# esp32_ornith_1_0_2.net
KiCad netlist of a schematic drawn in EAGLE
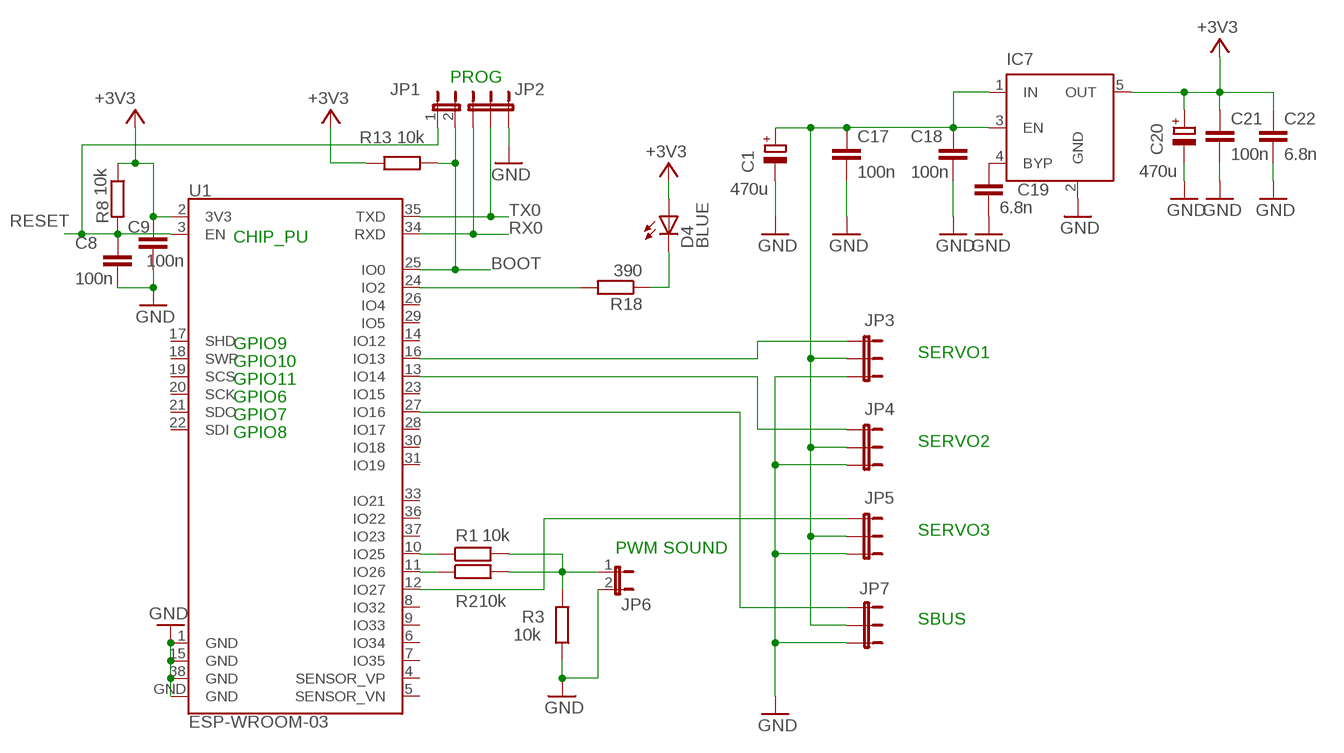
[diagram p0: schematic, sheet 1]

(export (version "E")
  (design (tool "Eeschema 10.0.6"))
  (components
    (comp (ref "C1")
      (value "470u")
      (footprint "eagle-import:SMC_D")
      (libsource (lib "eagle-import") (part "CPOL-EUSMCD"))
    )
    (comp (ref "C8")
      (value "100n")
      (footprint "eagle-import:C0603")
      (libsource (lib "eagle-import") (part "C-EUC0603"))
    )
    (comp (ref "C9")
      (value "100n")
      (footprint "eagle-import:C0603")
      (libsource (lib "eagle-import") (part "C-EUC0603"))
    )
    (comp (ref "C17")
      (value "100n")
      (footprint "eagle-import:C0603K")
      (libsource (lib "eagle-import") (part "C-EUC0603K"))
    )
    (comp (ref "C18")
      (value "100n")
      (footprint "eagle-import:C0603K")
      (libsource (lib "eagle-import") (part "C-EUC0603K"))
    )
    (comp (ref "C19")
      (value "6.8n")
      (footprint "eagle-import:C0603K")
      (libsource (lib "eagle-import") (part "C-EUC0603K"))
    )
    (comp (ref "C20")
      (value "470u")
      (footprint "eagle-import:SMC_D")
      (libsource (lib "eagle-import") (part "CPOL-EUSMCD"))
    )
    (comp (ref "C21")
      (value "100n")
      (footprint "eagle-import:C0603K")
      (libsource (lib "eagle-import") (part "C-EUC0603K"))
    )
    (comp (ref "C22")
      (value "6.8n")
      (footprint "eagle-import:C0603K")
      (libsource (lib "eagle-import") (part "C-EUC0603K"))
    )
    (comp (ref "D4")
      (value "BLUE")
      (footprint "eagle-import:LED-0603")
      (libsource (lib "eagle-import") (part "LED-BLUE0603"))
    )
    (comp (ref "IC7")
      (value "MIC5219XX")
      (footprint "eagle-import:SOT23-5")
      (libsource (lib "eagle-import") (part "MIC5219XX"))
    )
    (comp (ref "JP1")
      (value "JUMPER-2PTH")
      (footprint "eagle-import:1X02")
      (libsource (lib "eagle-import") (part "JUMPER-2PTH"))
    )
    (comp (ref "JP2")
      (value "JUMPER-3PTH")
      (footprint "eagle-import:1X03")
      (libsource (lib "eagle-import") (part "JUMPER-3PTH"))
    )
    (comp (ref "JP3")
      (value "JUMPER-3PTH")
      (footprint "eagle-import:1X03")
      (libsource (lib "eagle-import") (part "JUMPER-3PTH"))
    )
    (comp (ref "JP4")
      (value "JUMPER-3PTH")
      (footprint "eagle-import:1X03")
      (libsource (lib "eagle-import") (part "JUMPER-3PTH"))
    )
    (comp (ref "JP5")
      (value "JUMPER-3PTH")
      (footprint "eagle-import:1X03")
      (libsource (lib "eagle-import") (part "JUMPER-3PTH"))
    )
    (comp (ref "JP6")
      (value "JUMPER-2PTH")
      (footprint "eagle-import:1X02")
      (libsource (lib "eagle-import") (part "JUMPER-2PTH"))
    )
    (comp (ref "JP7")
      (value "JUMPER-3PTH")
      (footprint "eagle-import:1X03")
      (libsource (lib "eagle-import") (part "JUMPER-3PTH"))
    )
    (comp (ref "R1")
      (value "10k")
      (footprint "eagle-import:R0603")
      (libsource (lib "eagle-import") (part "R-EU_R0603"))
    )
    (comp (ref "R2")
      (value "10k")
      (footprint "eagle-import:R0603")
      (libsource (lib "eagle-import") (part "R-EU_R0603"))
    )
    (comp (ref "R3")
      (value "10k")
      (footprint "eagle-import:R0603")
      (libsource (lib "eagle-import") (part "R-EU_R0603"))
    )
    (comp (ref "R8")
      (value "10k")
      (footprint "eagle-import:R0603")
      (libsource (lib "eagle-import") (part "R-EU_R0603"))
    )
    (comp (ref "R13")
      (value "10k")
      (footprint "eagle-import:R0603")
      (libsource (lib "eagle-import") (part "R-EU_R0603"))
    )
    (comp (ref "R18")
      (value "390")
      (footprint "eagle-import:R0603")
      (libsource (lib "eagle-import") (part "R-EU_R0603"))
    )
    (comp (ref "U1")
      (value "ESP-WROOM-03")
      (footprint "eagle-import:ESP-WROOM-03")
      (libsource (lib "eagle-import") (part "ESP-WROOM-03"))
    )
  )
  (nets
    (net (code "1") (name "+3V3") (class "Default")
      (node (ref "C20") (pin "+") (pinfunction "+_+") (pintype "passive"))
      (node (ref "C21") (pin "1") (pinfunction "1_1") (pintype "passive"))
      (node (ref "C22") (pin "1") (pinfunction "1_1") (pintype "passive"))
      (node (ref "C9") (pin "1") (pinfunction "1_1") (pintype "passive"))
      (node (ref "D4") (pin "A") (pinfunction "A_A") (pintype "passive"))
      (node (ref "IC7") (pin "5") (pinfunction "OUT_5") (pintype "output"))
      (node (ref "R13") (pin "2") (pinfunction "2_2") (pintype "passive"))
      (node (ref "R8") (pin "1") (pinfunction "1_1") (pintype "passive"))
      (node (ref "U1") (pin "2") (pinfunction "3V3_2") (pintype "bidirectional"))
    )
    (net (code "2") (name "/BOOT") (class "Default")
      (node (ref "JP1") (pin "2") (pinfunction "2_2") (pintype "passive"))
      (node (ref "R13") (pin "1") (pinfunction "1_1") (pintype "passive"))
      (node (ref "U1") (pin "25") (pinfunction "IO0_25") (pintype "bidirectional"))
    )
    (net (code "3") (name "/RESET") (class "Default")
      (node (ref "C8") (pin "1") (pinfunction "1_1") (pintype "passive"))
      (node (ref "JP1") (pin "1") (pinfunction "1_1") (pintype "passive"))
      (node (ref "R8") (pin "2") (pinfunction "2_2") (pintype "passive"))
      (node (ref "U1") (pin "3") (pinfunction "EN_3") (pintype "bidirectional"))
    )
    (net (code "4") (name "/RX0") (class "Default")
      (node (ref "JP2") (pin "1") (pinfunction "1_1") (pintype "passive"))
      (node (ref "U1") (pin "34") (pinfunction "RXD_34") (pintype "bidirectional"))
    )
    (net (code "5") (name "/TX0") (class "Default")
      (node (ref "JP2") (pin "2") (pinfunction "2_2") (pintype "passive"))
      (node (ref "U1") (pin "35") (pinfunction "TXD_35") (pintype "bidirectional"))
    )
    (net (code "6") (name "GND") (class "Default")
      (node (ref "C1") (pin "-") (pinfunction "-_-") (pintype "passive"))
      (node (ref "C17") (pin "2") (pinfunction "2_2") (pintype "passive"))
      (node (ref "C18") (pin "2") (pinfunction "2_2") (pintype "passive"))
      (node (ref "C19") (pin "2") (pinfunction "2_2") (pintype "passive"))
      (node (ref "C20") (pin "-") (pinfunction "-_-") (pintype "passive"))
      (node (ref "C21") (pin "2") (pinfunction "2_2") (pintype "passive"))
      (node (ref "C22") (pin "2") (pinfunction "2_2") (pintype "passive"))
      (node (ref "C8") (pin "2") (pinfunction "2_2") (pintype "passive"))
      (node (ref "C9") (pin "2") (pinfunction "2_2") (pintype "passive"))
      (node (ref "IC7") (pin "2") (pinfunction "GND_2") (pintype "power_in"))
      (node (ref "JP2") (pin "3") (pinfunction "3_3") (pintype "passive"))
      (node (ref "JP3") (pin "1") (pinfunction "1_1") (pintype "passive"))
      (node (ref "JP4") (pin "1") (pinfunction "1_1") (pintype "passive"))
      (node (ref "JP5") (pin "1") (pinfunction "1_1") (pintype "passive"))
      (node (ref "JP6") (pin "2") (pinfunction "2_2") (pintype "passive"))
      (node (ref "JP7") (pin "3") (pinfunction "3_3") (pintype "passive"))
      (node (ref "R3") (pin "1") (pinfunction "1_1") (pintype "passive"))
      (node (ref "U1") (pin "1") (pinfunction "GND_1") (pintype "bidirectional"))
      (node (ref "U1") (pin "15") (pinfunction "GND_15") (pintype "bidirectional"))
      (node (ref "U1") (pin "38") (pinfunction "GND_38") (pintype "bidirectional"))
      (node (ref "U1") (pin "GND") (pinfunction "GND_GND") (pintype "bidirectional"))
    )
    (net (code "7") (name "Net-(D4-PadC)") (class "Default")
      (node (ref "D4") (pin "C") (pinfunction "C_C") (pintype "passive"))
      (node (ref "R18") (pin "1") (pinfunction "1_1") (pintype "passive"))
    )
    (net (code "8") (name "Net-(IC7-BYP)") (class "Default")
      (node (ref "C19") (pin "1") (pinfunction "1_1") (pintype "passive"))
      (node (ref "IC7") (pin "4") (pinfunction "BYP_4") (pintype "passive"))
    )
    (net (code "9") (name "Net-(IC7-EN)") (class "Default")
      (node (ref "C1") (pin "+") (pinfunction "+_+") (pintype "passive"))
      (node (ref "C17") (pin "1") (pinfunction "1_1") (pintype "passive"))
      (node (ref "C18") (pin "1") (pinfunction "1_1") (pintype "passive"))
      (node (ref "IC7") (pin "1") (pinfunction "IN_1") (pintype "input"))
      (node (ref "IC7") (pin "3") (pinfunction "EN_3") (pintype "input"))
      (node (ref "JP3") (pin "2") (pinfunction "2_2") (pintype "passive"))
      (node (ref "JP4") (pin "2") (pinfunction "2_2") (pintype "passive"))
      (node (ref "JP5") (pin "2") (pinfunction "2_2") (pintype "passive"))
      (node (ref "JP7") (pin "2") (pinfunction "2_2") (pintype "passive"))
    )
    (net (code "10") (name "Net-(JP6-Pad1)") (class "Default")
      (node (ref "JP6") (pin "1") (pinfunction "1_1") (pintype "passive"))
      (node (ref "R1") (pin "2") (pinfunction "2_2") (pintype "passive"))
      (node (ref "R2") (pin "2") (pinfunction "2_2") (pintype "passive"))
      (node (ref "R3") (pin "2") (pinfunction "2_2") (pintype "passive"))
    )
    (net (code "11") (name "Net-(U1-IO2)") (class "Default")
      (node (ref "R18") (pin "2") (pinfunction "2_2") (pintype "passive"))
      (node (ref "U1") (pin "24") (pinfunction "IO2_24") (pintype "bidirectional"))
    )
    (net (code "12") (name "Net-(U1-IO13)") (class "Default")
      (node (ref "JP3") (pin "3") (pinfunction "3_3") (pintype "passive"))
      (node (ref "U1") (pin "16") (pinfunction "IO13_16") (pintype "bidirectional"))
    )
    (net (code "13") (name "Net-(U1-IO14)") (class "Default")
      (node (ref "JP4") (pin "3") (pinfunction "3_3") (pintype "passive"))
      (node (ref "U1") (pin "13") (pinfunction "IO14_13") (pintype "bidirectional"))
    )
    (net (code "14") (name "Net-(U1-IO16)") (class "Default")
      (node (ref "JP7") (pin "1") (pinfunction "1_1") (pintype "passive"))
      (node (ref "U1") (pin "27") (pinfunction "IO16_27") (pintype "bidirectional"))
    )
    (net (code "15") (name "Net-(U1-IO25)") (class "Default")
      (node (ref "R1") (pin "1") (pinfunction "1_1") (pintype "passive"))
      (node (ref "U1") (pin "10") (pinfunction "IO25_10") (pintype "bidirectional"))
    )
    (net (code "16") (name "Net-(U1-IO26)") (class "Default")
      (node (ref "R2") (pin "1") (pinfunction "1_1") (pintype "passive"))
      (node (ref "U1") (pin "11") (pinfunction "IO26_11") (pintype "bidirectional"))
    )
    (net (code "17") (name "Net-(U1-IO27)") (class "Default")
      (node (ref "JP5") (pin "3") (pinfunction "3_3") (pintype "passive"))
      (node (ref "U1") (pin "12") (pinfunction "IO27_12") (pintype "bidirectional"))
    )
    (net (code "18") (name "unconnected-(U1-IO4-Pad26)") (class "Default")
      (node (ref "U1") (pin "26") (pinfunction "IO4_26") (pintype "bidirectional"))
    )
    (net (code "19") (name "unconnected-(U1-IO5-Pad29)") (class "Default")
      (node (ref "U1") (pin "29") (pinfunction "IO5_29") (pintype "bidirectional"))
    )
    (net (code "20") (name "unconnected-(U1-IO12-Pad14)") (class "Default")
      (node (ref "U1") (pin "14") (pinfunction "IO12_14") (pintype "bidirectional"))
    )
    (net (code "21") (name "unconnected-(U1-IO15-Pad23)") (class "Default")
      (node (ref "U1") (pin "23") (pinfunction "IO15_23") (pintype "bidirectional"))
    )
    (net (code "22") (name "unconnected-(U1-IO17-Pad28)") (class "Default")
      (node (ref "U1") (pin "28") (pinfunction "IO17_28") (pintype "bidirectional"))
    )
    (net (code "23") (name "unconnected-(U1-IO18-Pad30)") (class "Default")
      (node (ref "U1") (pin "30") (pinfunction "IO18_30") (pintype "bidirectional"))
    )
    (net (code "24") (name "unconnected-(U1-IO19-Pad31)") (class "Default")
      (node (ref "U1") (pin "31") (pinfunction "IO19_31") (pintype "bidirectional"))
    )
    (net (code "25") (name "unconnected-(U1-IO21-Pad33)") (class "Default")
      (node (ref "U1") (pin "33") (pinfunction "IO21_33") (pintype "bidirectional"))
    )
    (net (code "26") (name "unconnected-(U1-IO22-Pad36)") (class "Default")
      (node (ref "U1") (pin "36") (pinfunction "IO22_36") (pintype "bidirectional"))
    )
    (net (code "27") (name "unconnected-(U1-IO23-Pad37)") (class "Default")
      (node (ref "U1") (pin "37") (pinfunction "IO23_37") (pintype "bidirectional"))
    )
    (net (code "28") (name "unconnected-(U1-IO32-Pad8)") (class "Default")
      (node (ref "U1") (pin "8") (pinfunction "IO32_8") (pintype "bidirectional"))
    )
    (net (code "29") (name "unconnected-(U1-IO33-Pad9)") (class "Default")
      (node (ref "U1") (pin "9") (pinfunction "IO33_9") (pintype "bidirectional"))
    )
    (net (code "30") (name "unconnected-(U1-IO34-Pad6)") (class "Default")
      (node (ref "U1") (pin "6") (pinfunction "IO34_6") (pintype "bidirectional"))
    )
    (net (code "31") (name "unconnected-(U1-IO35-Pad7)") (class "Default")
      (node (ref "U1") (pin "7") (pinfunction "IO35_7") (pintype "bidirectional"))
    )
    (net (code "32") (name "unconnected-(U1-SCK-Pad20)") (class "Default")
      (node (ref "U1") (pin "20") (pinfunction "SCK_20") (pintype "bidirectional"))
    )
    (net (code "33") (name "unconnected-(U1-SCS-Pad19)") (class "Default")
      (node (ref "U1") (pin "19") (pinfunction "SCS_19") (pintype "bidirectional"))
    )
    (net (code "34") (name "unconnected-(U1-SDI-Pad22)") (class "Default")
      (node (ref "U1") (pin "22") (pinfunction "SDI_22") (pintype "bidirectional"))
    )
    (net (code "35") (name "unconnected-(U1-SDO-Pad21)") (class "Default")
      (node (ref "U1") (pin "21") (pinfunction "SDO_21") (pintype "bidirectional"))
    )
    (net (code "36") (name "unconnected-(U1-SENSOR_VN-Pad5)") (class "Default")
      (node (ref "U1") (pin "5") (pinfunction "SENSOR_VN_5") (pintype "bidirectional"))
    )
    (net (code "37") (name "unconnected-(U1-SENSOR_VP-Pad4)") (class "Default")
      (node (ref "U1") (pin "4") (pinfunction "SENSOR_VP_4") (pintype "bidirectional"))
    )
    (net (code "38") (name "unconnected-(U1-SHD-Pad17)") (class "Default")
      (node (ref "U1") (pin "17") (pinfunction "SHD_17") (pintype "bidirectional"))
    )
    (net (code "39") (name "unconnected-(U1-SWP-Pad18)") (class "Default")
      (node (ref "U1") (pin "18") (pinfunction "SWP_18") (pintype "bidirectional"))
    )
  )
)
